# Vstupy.net
KiCad netlist of a schematic drawn in Altium Designer
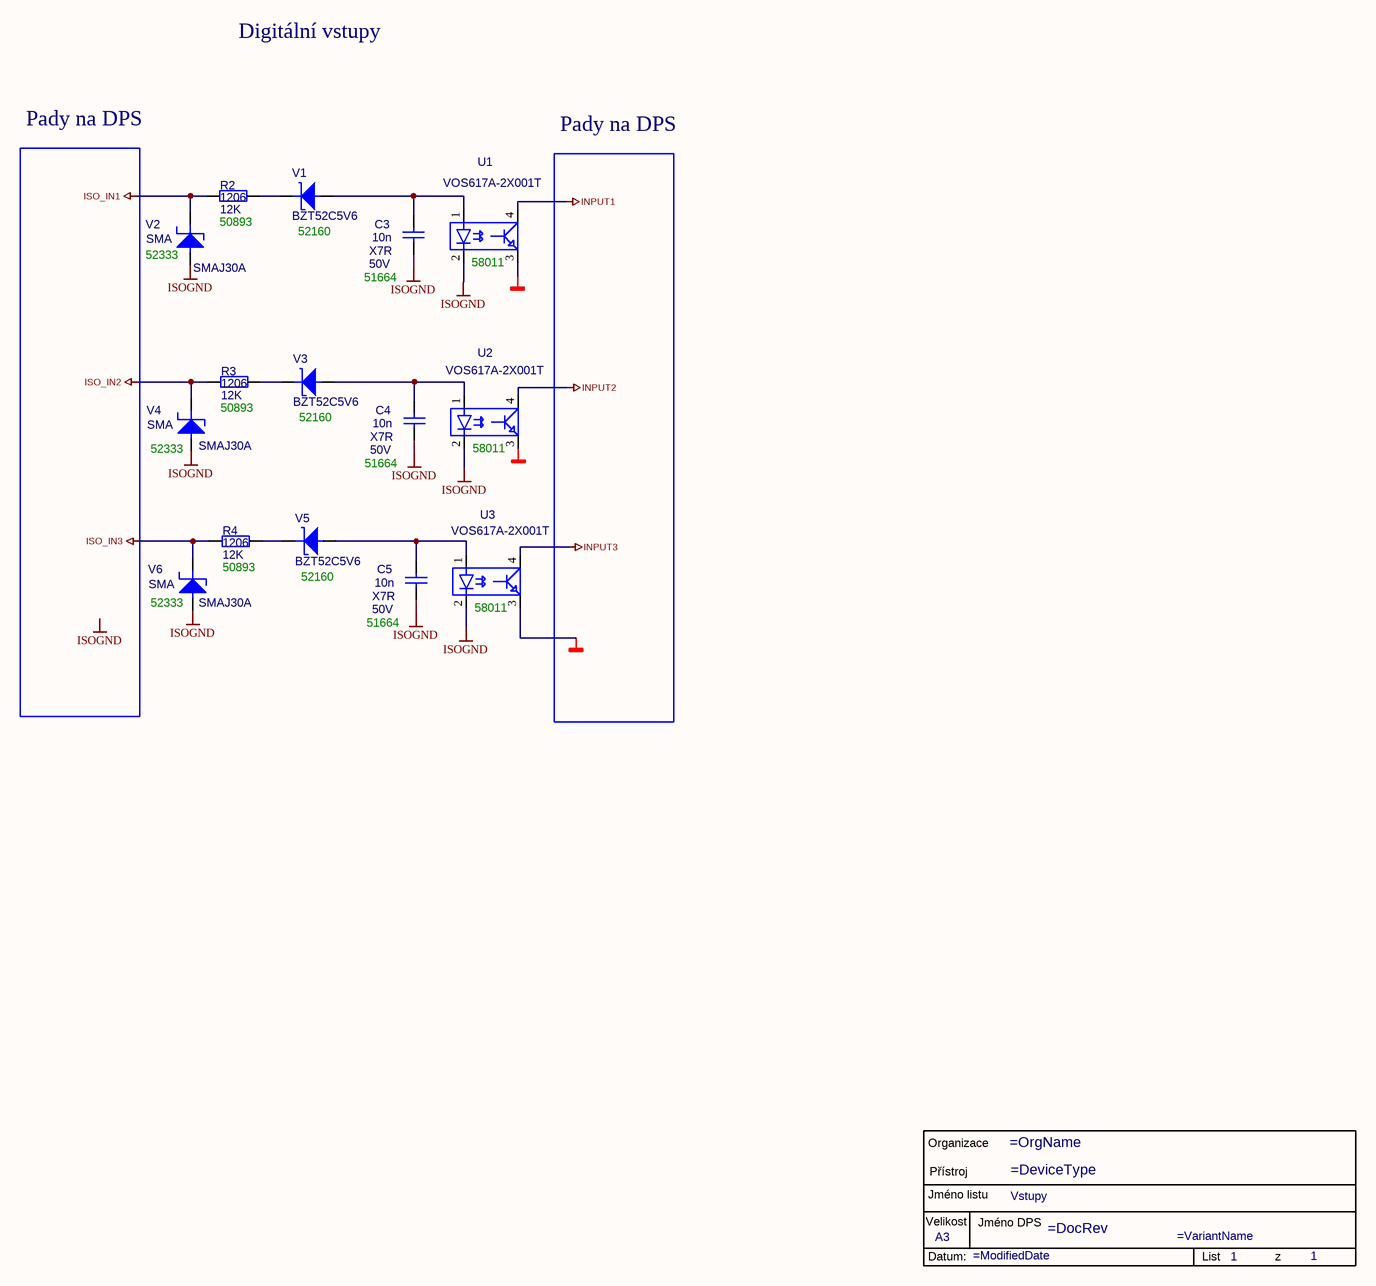
[diagram p0: Vstupy.SchDoc]

(export (version "E")
  (design (tool "Eeschema 10.0.6"))
  (components
    (comp (ref "*") (value "RAZITKO") (libsource (lib "AAAA_Library") (part "RAZITKO")))
    (comp (ref "C3")
      (value "10n")
      (footprint "Z0603")
      (fields
        (field (name "VOLTAGE") "50V")
        (field (name "TOLERANCE") "X7R")
        (field (name "MEGA_ID") "51664")
      )
      (libsource (lib "*") (part "C"))
    )
    (comp (ref "C4")
      (value "10n")
      (footprint "Z0603")
      (fields
        (field (name "VOLTAGE") "50V")
        (field (name "TOLERANCE") "X7R")
        (field (name "MEGA_ID") "51664")
      )
      (libsource (lib "*") (part "C"))
    )
    (comp (ref "C5")
      (value "10n")
      (footprint "Z0603")
      (fields
        (field (name "VOLTAGE") "50V")
        (field (name "TOLERANCE") "X7R")
        (field (name "MEGA_ID") "51664")
      )
      (libsource (lib "*") (part "C"))
    )
    (comp (ref "R2")
      (value "12K")
      (footprint "Z1206")
      (fields (field (name "MEGA_ID") "50893") (field (name "SIZE") "1206") (field (name "TOLERANCE") "1%"))
      (libsource (lib "*") (part "R"))
    )
    (comp (ref "R3")
      (value "12K")
      (footprint "Z1206")
      (fields (field (name "MEGA_ID") "50893") (field (name "SIZE") "1206") (field (name "TOLERANCE") "1%"))
      (libsource (lib "*") (part "R"))
    )
    (comp (ref "R4")
      (value "12K")
      (footprint "Z1206")
      (fields (field (name "MEGA_ID") "50893") (field (name "SIZE") "1206") (field (name "TOLERANCE") "1%"))
      (libsource (lib "*") (part "R"))
    )
    (comp (ref "U1")
      (value "VOS617A-2X001T")
      (footprint "ZSSOP-4")
      (fields
        (field (name "MEGA_ID") "58011")
        (field (name "VOLTAGE") "Uce=80V, Uizol =3.75 kV")
        (field (name "POWER") "If=50mA, Ic=50mA")
      )
      (libsource (lib "*") (part "OPTO1_1"))
    )
    (comp (ref "U2")
      (value "VOS617A-2X001T")
      (footprint "ZSSOP-4")
      (fields
        (field (name "MEGA_ID") "58011")
        (field (name "VOLTAGE") "Uce=80V, Uizol =3.75 kV")
        (field (name "POWER") "If=50mA, Ic=50mA")
      )
      (libsource (lib "*") (part "OPTO1_1"))
    )
    (comp (ref "U3")
      (value "VOS617A-2X001T")
      (footprint "ZSSOP-4")
      (fields
        (field (name "MEGA_ID") "58011")
        (field (name "VOLTAGE") "Uce=80V, Uizol =3.75 kV")
        (field (name "POWER") "If=50mA, Ic=50mA")
      )
      (libsource (lib "*") (part "OPTO1_1"))
    )
    (comp (ref "V1")
      (value "BZT52C5V6")
      (footprint "ZSOD123")
      (fields (field (name "MEGA_ID") "52160") (field (name "VOLTAGE") "5V6") (field (name "POWER") "0.3W"))
      (libsource (lib "*") (part "DIODE ZENER"))
    )
    (comp (ref "V2")
      (value "SMAJ30A")
      (footprint "ZSMA")
      (fields
        (field (name "SIZE") "SMA")
        (field (name "MEGA_ID") "52333")
        (field (name "MANUFACTURER") "P4SMAJ30A")
        (field (name "VOLTAGE") "30V")
        (field (name "POWER") "400W Uni")
      )
      (libsource (lib "*") (part "DIODE TRANSIL"))
    )
    (comp (ref "V3")
      (value "BZT52C5V6")
      (footprint "ZSOD123")
      (fields (field (name "MEGA_ID") "52160") (field (name "VOLTAGE") "5V6") (field (name "POWER") "0.3W"))
      (libsource (lib "*") (part "DIODE ZENER"))
    )
    (comp (ref "V4")
      (value "SMAJ30A")
      (footprint "ZSMA")
      (fields
        (field (name "SIZE") "SMA")
        (field (name "MEGA_ID") "52333")
        (field (name "MANUFACTURER") "P4SMAJ30A")
        (field (name "VOLTAGE") "30V")
        (field (name "POWER") "400W Uni")
      )
      (libsource (lib "*") (part "DIODE TRANSIL"))
    )
    (comp (ref "V5")
      (value "BZT52C5V6")
      (footprint "ZSOD123")
      (fields (field (name "MEGA_ID") "52160") (field (name "VOLTAGE") "5V6") (field (name "POWER") "0.3W"))
      (libsource (lib "*") (part "DIODE ZENER"))
    )
    (comp (ref "V6")
      (value "SMAJ30A")
      (footprint "ZSMA")
      (fields
        (field (name "SIZE") "SMA")
        (field (name "MEGA_ID") "52333")
        (field (name "MANUFACTURER") "P4SMAJ30A")
        (field (name "VOLTAGE") "30V")
        (field (name "POWER") "400W Uni")
      )
      (libsource (lib "*") (part "DIODE TRANSIL"))
    )
  )
  (nets
    (net (code "1") (name "GND") (class "Default")
      (node (ref "U1") (pin "3") (pinfunction "3_3") (pintype "passive"))
      (node (ref "U2") (pin "3") (pinfunction "3_3") (pintype "passive"))
      (node (ref "U3") (pin "3") (pinfunction "3_3") (pintype "passive"))
    )
    (net (code "2") (name "INPUT1") (class "Default")
      (node (ref "U1") (pin "4") (pinfunction "4_4") (pintype "passive"))
    )
    (net (code "3") (name "INPUT2") (class "Default")
      (node (ref "U2") (pin "4") (pinfunction "4_4") (pintype "passive"))
    )
    (net (code "4") (name "INPUT3") (class "Default")
      (node (ref "U3") (pin "4") (pinfunction "4_4") (pintype "passive"))
    )
    (net (code "5") (name "ISOGND") (class "Default")
      (node (ref "C3") (pin "2") (pinfunction "2_2") (pintype "passive"))
      (node (ref "C4") (pin "2") (pinfunction "2_2") (pintype "passive"))
      (node (ref "C5") (pin "2") (pinfunction "2_2") (pintype "passive"))
      (node (ref "U1") (pin "2") (pinfunction "2_2") (pintype "passive"))
      (node (ref "U2") (pin "2") (pinfunction "2_2") (pintype "passive"))
      (node (ref "U3") (pin "2") (pinfunction "2_2") (pintype "passive"))
      (node (ref "V2") (pin "1") (pinfunction "A_1") (pintype "passive"))
      (node (ref "V4") (pin "1") (pinfunction "A_1") (pintype "passive"))
      (node (ref "V6") (pin "1") (pinfunction "A_1") (pintype "passive"))
    )
    (net (code "6") (name "ISO_IN1") (class "Default")
      (node (ref "R2") (pin "1") (pinfunction "1_1") (pintype "passive"))
      (node (ref "V2") (pin "2") (pinfunction "K_2") (pintype "passive"))
    )
    (net (code "7") (name "ISO_IN2") (class "Default")
      (node (ref "R3") (pin "1") (pinfunction "1_1") (pintype "passive"))
      (node (ref "V4") (pin "2") (pinfunction "K_2") (pintype "passive"))
    )
    (net (code "8") (name "ISO_IN3") (class "Default")
      (node (ref "R4") (pin "1") (pinfunction "1_1") (pintype "passive"))
      (node (ref "V6") (pin "2") (pinfunction "K_2") (pintype "passive"))
    )
    (net (code "9") (name "Net-(V1-A)") (class "Default")
      (node (ref "C3") (pin "1") (pinfunction "1_1") (pintype "passive"))
      (node (ref "U1") (pin "1") (pinfunction "1_1") (pintype "passive"))
      (node (ref "V1") (pin "1") (pinfunction "A_1") (pintype "passive"))
    )
    (net (code "10") (name "Net-(V1-K)") (class "Default")
      (node (ref "R2") (pin "2") (pinfunction "2_2") (pintype "passive"))
      (node (ref "V1") (pin "2") (pinfunction "K_2") (pintype "passive"))
    )
    (net (code "11") (name "Net-(V3-A)") (class "Default")
      (node (ref "C4") (pin "1") (pinfunction "1_1") (pintype "passive"))
      (node (ref "U2") (pin "1") (pinfunction "1_1") (pintype "passive"))
      (node (ref "V3") (pin "1") (pinfunction "A_1") (pintype "passive"))
    )
    (net (code "12") (name "Net-(V3-K)") (class "Default")
      (node (ref "R3") (pin "2") (pinfunction "2_2") (pintype "passive"))
      (node (ref "V3") (pin "2") (pinfunction "K_2") (pintype "passive"))
    )
    (net (code "13") (name "Net-(V5-A)") (class "Default")
      (node (ref "C5") (pin "1") (pinfunction "1_1") (pintype "passive"))
      (node (ref "U3") (pin "1") (pinfunction "1_1") (pintype "passive"))
      (node (ref "V5") (pin "1") (pinfunction "A_1") (pintype "passive"))
    )
    (net (code "14") (name "Net-(V5-K)") (class "Default")
      (node (ref "R4") (pin "2") (pinfunction "2_2") (pintype "passive"))
      (node (ref "V5") (pin "2") (pinfunction "K_2") (pintype "passive"))
    )
  )
)
